# Dashboard_rev3.net
KiCad netlist of a schematic drawn in EAGLE
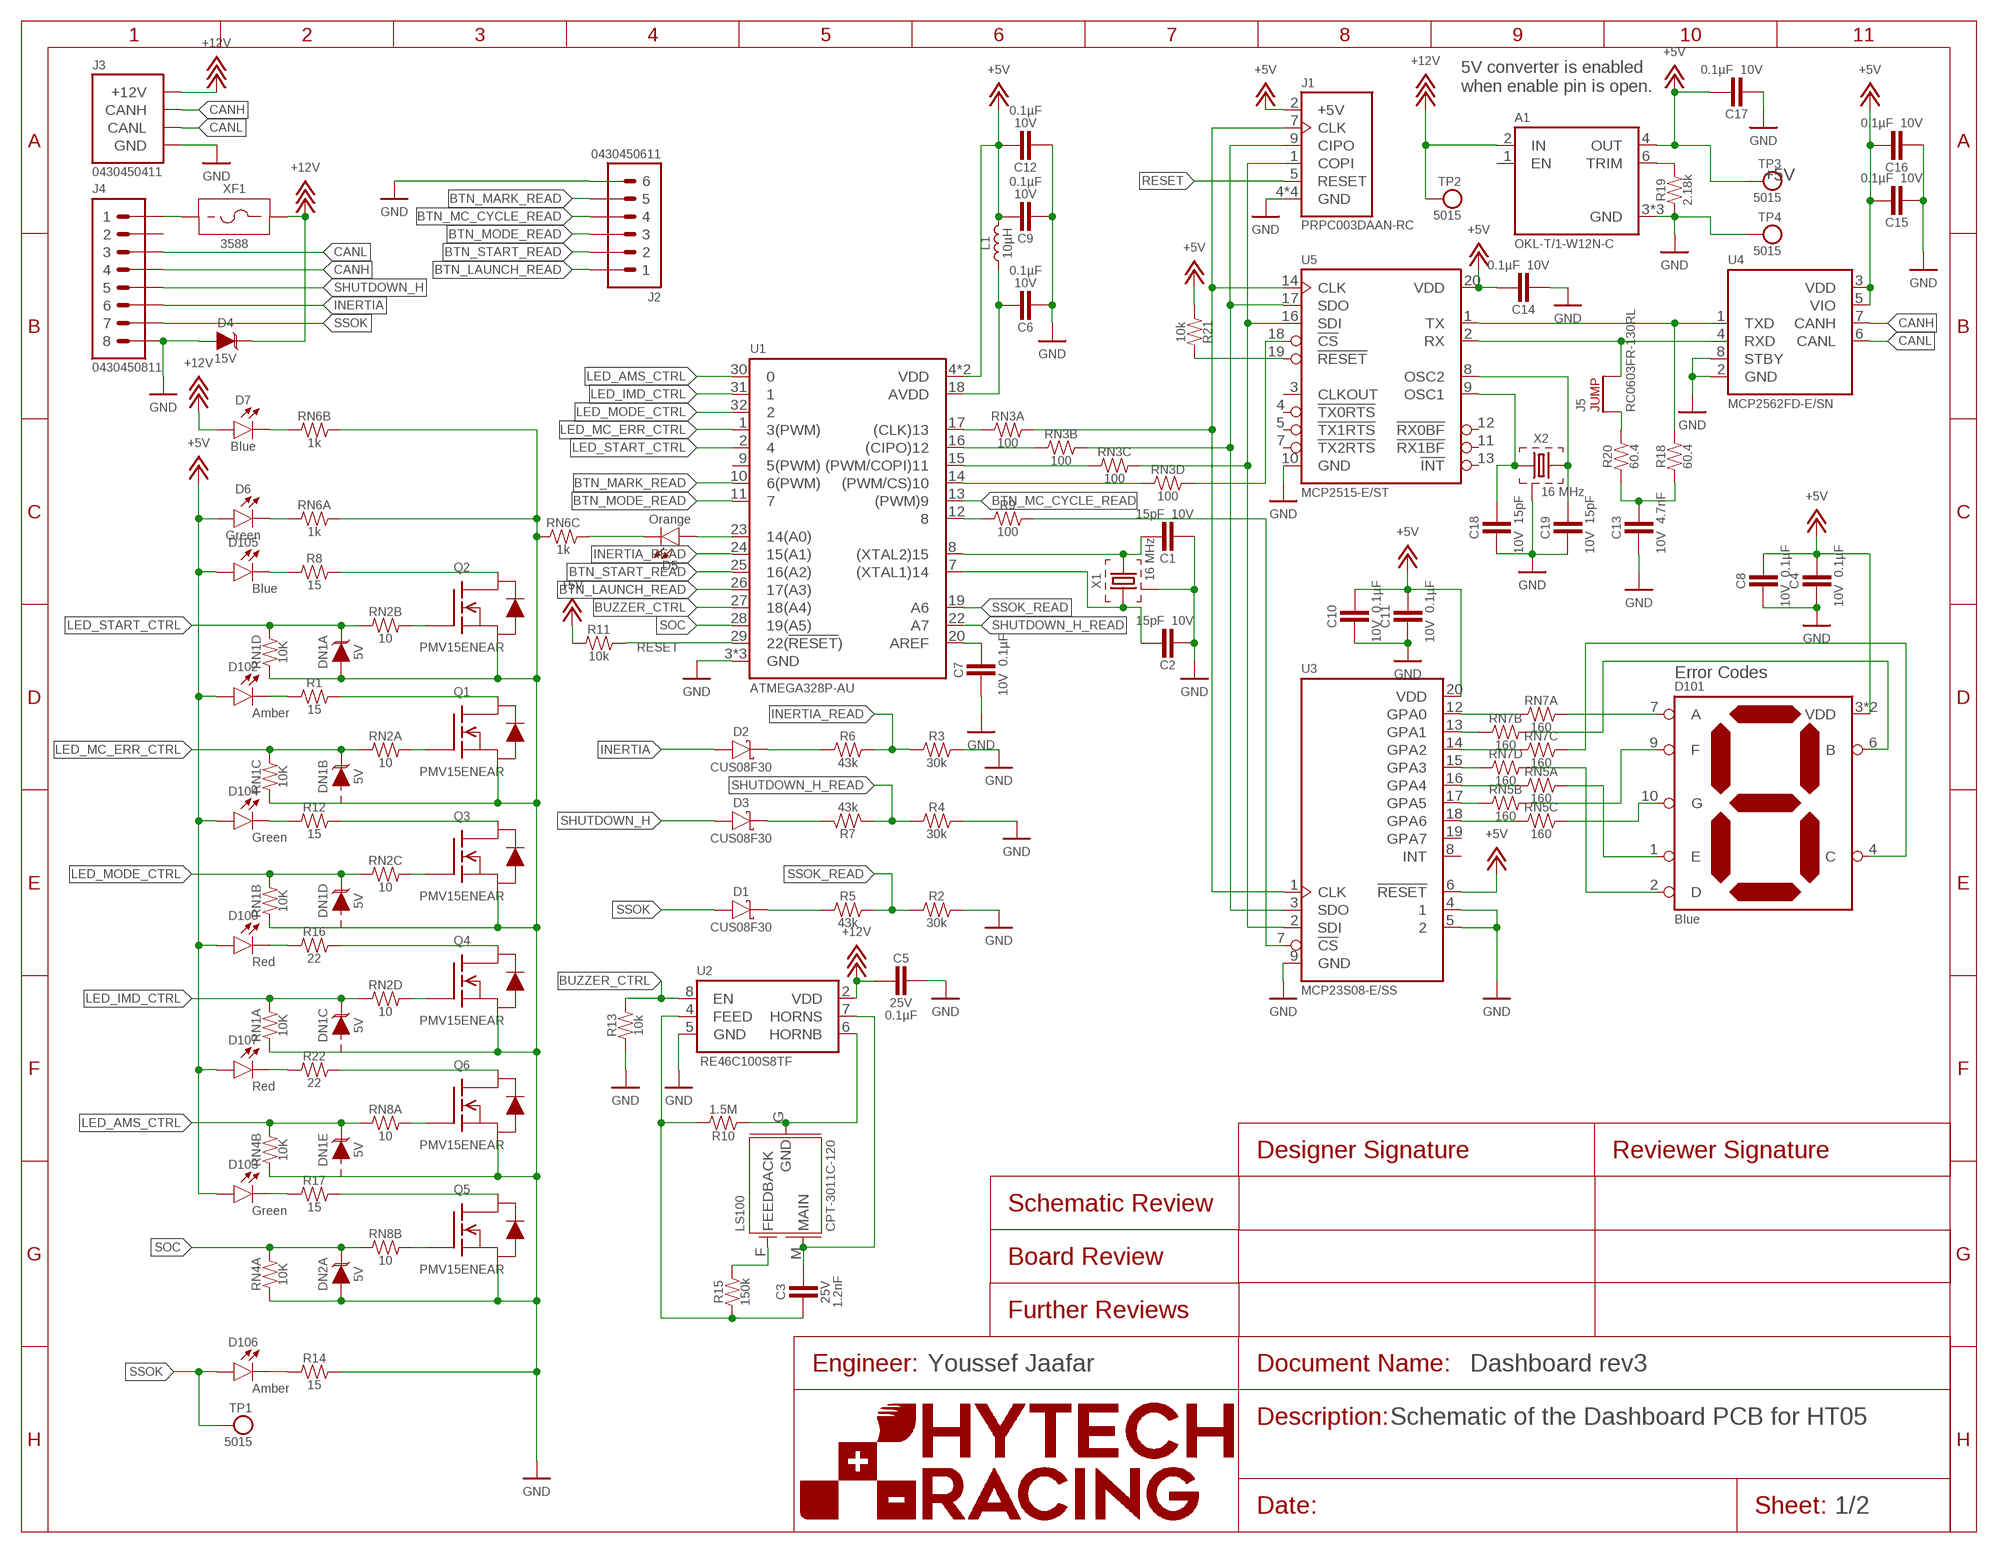
[diagram p0: schematic, sheet 1]
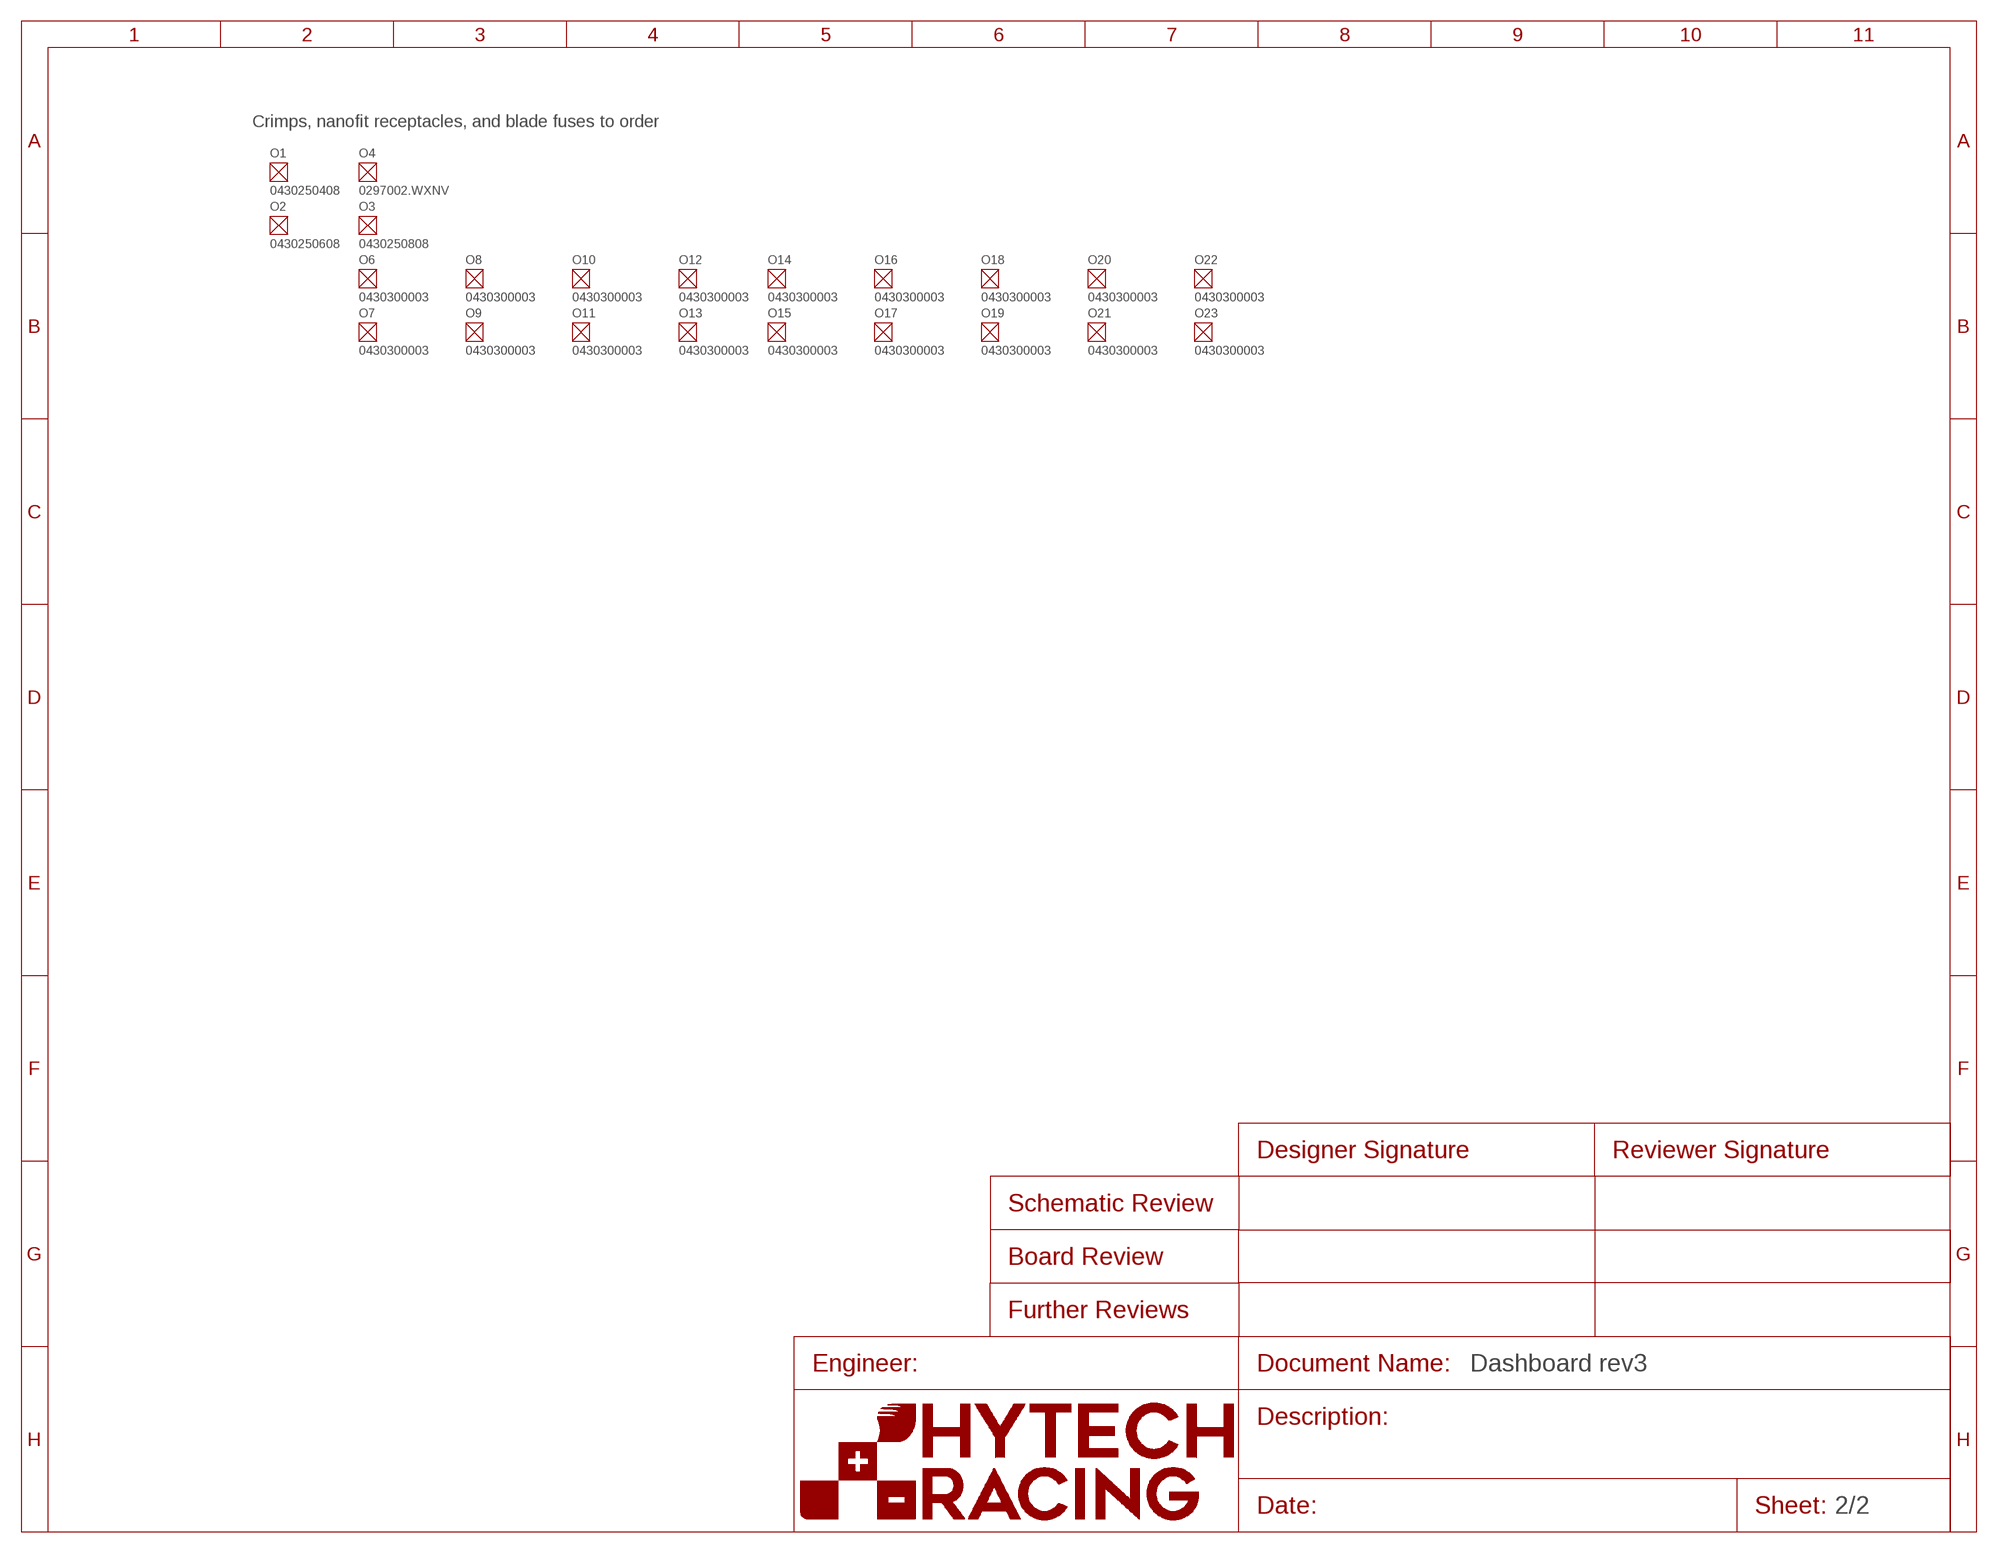
[diagram p1: schematic, sheet 2]

(export (version "E")
  (design (tool "Eeschema 10.0.6"))
  (components
    (comp (ref "A1")
      (value "OKL-T/1-W12N-COKL")
      (footprint "eagle-import:OKL-T_1-W12")
      (fields
        (field (name "MANUFACTURER") "Murata Power Solutions Inc.")
        (field (name "MPN") "OKL-T/1-W12N-C")
      )
      (libsource (lib "eagle-import") (part "OKL-OKLT/1-W12N-C"))
    )
    (comp (ref "C1")
      (value "CAPACITOR_0603_10V_15PF")
      (footprint "eagle-import:0603-CAP")
      (fields
        (field (name "CAPACITANCE") "15pF")
        (field (name "MANUFACTURER") "Vishay Vitramon")
        (field (name "MPN") "VJ0603A150FXQPW1BC")
        (field (name "TOLERANCE") "1%")
        (field (name "VOLTAGE") "10V")
      )
      (libsource (lib "eagle-import") (part "CAPACITOR_?_060310V_15PF"))
    )
    (comp (ref "C2")
      (value "CAPACITOR_0603_10V_15PF")
      (footprint "eagle-import:0603-CAP")
      (fields
        (field (name "CAPACITANCE") "15pF")
        (field (name "MANUFACTURER") "Vishay Vitramon")
        (field (name "MPN") "VJ0603A150FXQPW1BC")
        (field (name "TOLERANCE") "1%")
        (field (name "VOLTAGE") "10V")
      )
      (libsource (lib "eagle-import") (part "CAPACITOR_?_060310V_15PF"))
    )
    (comp (ref "C3")
      (value "CAPACITOR_0603_25V_1.2NF")
      (footprint "eagle-import:0603-CAP")
      (fields
        (field (name "CAPACITANCE") "1.2nF")
        (field (name "MANUFACTURER") "YAGEO")
        (field (name "MPN") "CC0603KRX7R8BB122")
        (field (name "TOLERANCE") "10%")
        (field (name "VOLTAGE") "25V")
      )
      (libsource (lib "eagle-import") (part "CAPACITOR_?_060325V_1.2NF"))
    )
    (comp (ref "C4")
      (value "CAPACITOR_0603_10V_0.1UF")
      (footprint "eagle-import:0603-CAP")
      (fields
        (field (name "CAPACITANCE") "0.1µF")
        (field (name "MANUFACTURER") "Vishay Vitramon")
        (field (name "MPN") "VJ0603Y104JXQPW1BC")
        (field (name "TOLERANCE") "5%")
        (field (name "VOLTAGE") "10V")
      )
      (libsource (lib "eagle-import") (part "CAPACITOR_?_060310V_0.1UF"))
    )
    (comp (ref "C5")
      (value "CAPACITOR_0603_25V_0.1UF")
      (footprint "eagle-import:0603-CAP")
      (fields
        (field (name "CAPACITANCE") "0.1µF")
        (field (name "MANUFACTURER") "Samsung Electro-Mechanics")
        (field (name "MPN") "CL10B104KA8NNNC")
        (field (name "TOLERANCE") "10%")
        (field (name "VOLTAGE") "25V")
      )
      (libsource (lib "eagle-import") (part "CAPACITOR_?_060325V_0.1UF"))
    )
    (comp (ref "C6")
      (value "CAPACITOR_0603_10V_0.1UF")
      (footprint "eagle-import:0603-CAP")
      (fields
        (field (name "CAPACITANCE") "0.1µF")
        (field (name "MANUFACTURER") "Vishay Vitramon")
        (field (name "MPN") "VJ0603Y104JXQPW1BC")
        (field (name "TOLERANCE") "5%")
        (field (name "VOLTAGE") "10V")
      )
      (libsource (lib "eagle-import") (part "CAPACITOR_?_060310V_0.1UF"))
    )
    (comp (ref "C7")
      (value "CAPACITOR_0603_10V_0.1UF")
      (footprint "eagle-import:0603-CAP")
      (fields
        (field (name "CAPACITANCE") "0.1µF")
        (field (name "MANUFACTURER") "Vishay Vitramon")
        (field (name "MPN") "VJ0603Y104JXQPW1BC")
        (field (name "TOLERANCE") "5%")
        (field (name "VOLTAGE") "10V")
      )
      (libsource (lib "eagle-import") (part "CAPACITOR_?_060310V_0.1UF"))
    )
    (comp (ref "C8")
      (value "CAPACITOR_0603_10V_0.1UF")
      (footprint "eagle-import:0603-CAP")
      (fields
        (field (name "CAPACITANCE") "0.1µF")
        (field (name "MANUFACTURER") "Vishay Vitramon")
        (field (name "MPN") "VJ0603Y104JXQPW1BC")
        (field (name "TOLERANCE") "5%")
        (field (name "VOLTAGE") "10V")
      )
      (libsource (lib "eagle-import") (part "CAPACITOR_?_060310V_0.1UF"))
    )
    (comp (ref "C9")
      (value "CAPACITOR_0603_10V_0.1UF")
      (footprint "eagle-import:0603-CAP")
      (fields
        (field (name "CAPACITANCE") "0.1µF")
        (field (name "MANUFACTURER") "Vishay Vitramon")
        (field (name "MPN") "VJ0603Y104JXQPW1BC")
        (field (name "TOLERANCE") "5%")
        (field (name "VOLTAGE") "10V")
      )
      (libsource (lib "eagle-import") (part "CAPACITOR_?_060310V_0.1UF"))
    )
    (comp (ref "C10")
      (value "CAPACITOR_0603_10V_0.1UF")
      (footprint "eagle-import:0603-CAP")
      (fields
        (field (name "CAPACITANCE") "0.1µF")
        (field (name "MANUFACTURER") "Vishay Vitramon")
        (field (name "MPN") "VJ0603Y104JXQPW1BC")
        (field (name "TOLERANCE") "5%")
        (field (name "VOLTAGE") "10V")
      )
      (libsource (lib "eagle-import") (part "CAPACITOR_?_060310V_0.1UF"))
    )
    (comp (ref "C11")
      (value "CAPACITOR_0603_10V_0.1UF")
      (footprint "eagle-import:0603-CAP")
      (fields
        (field (name "CAPACITANCE") "0.1µF")
        (field (name "MANUFACTURER") "Vishay Vitramon")
        (field (name "MPN") "VJ0603Y104JXQPW1BC")
        (field (name "TOLERANCE") "5%")
        (field (name "VOLTAGE") "10V")
      )
      (libsource (lib "eagle-import") (part "CAPACITOR_?_060310V_0.1UF"))
    )
    (comp (ref "C12")
      (value "CAPACITOR_0603_10V_0.1UF")
      (footprint "eagle-import:0603-CAP")
      (fields
        (field (name "CAPACITANCE") "0.1µF")
        (field (name "MANUFACTURER") "Vishay Vitramon")
        (field (name "MPN") "VJ0603Y104JXQPW1BC")
        (field (name "TOLERANCE") "5%")
        (field (name "VOLTAGE") "10V")
      )
      (libsource (lib "eagle-import") (part "CAPACITOR_?_060310V_0.1UF"))
    )
    (comp (ref "C13")
      (value "CAPACITOR_0603_10V_4.7NF")
      (footprint "eagle-import:0603-CAP")
      (fields
        (field (name "CAPACITANCE") "4.7nF")
        (field (name "MANUFACTURER") "Würth Elektronik")
        (field (name "MPN") "885012206012")
        (field (name "TOLERANCE") "10%")
        (field (name "VOLTAGE") "10V")
      )
      (libsource (lib "eagle-import") (part "CAPACITOR_?_060310V_4.7NF"))
    )
    (comp (ref "C14")
      (value "CAPACITOR_0603_10V_0.1UF")
      (footprint "eagle-import:0603-CAP")
      (fields
        (field (name "CAPACITANCE") "0.1µF")
        (field (name "MANUFACTURER") "Vishay Vitramon")
        (field (name "MPN") "VJ0603Y104JXQPW1BC")
        (field (name "TOLERANCE") "5%")
        (field (name "VOLTAGE") "10V")
      )
      (libsource (lib "eagle-import") (part "CAPACITOR_?_060310V_0.1UF"))
    )
    (comp (ref "C15")
      (value "CAPACITOR_0603_10V_0.1UF")
      (footprint "eagle-import:0603-CAP")
      (fields
        (field (name "CAPACITANCE") "0.1µF")
        (field (name "MANUFACTURER") "Vishay Vitramon")
        (field (name "MPN") "VJ0603Y104JXQPW1BC")
        (field (name "TOLERANCE") "5%")
        (field (name "VOLTAGE") "10V")
      )
      (libsource (lib "eagle-import") (part "CAPACITOR_?_060310V_0.1UF"))
    )
    (comp (ref "C16")
      (value "CAPACITOR_0603_10V_0.1UF")
      (footprint "eagle-import:0603-CAP")
      (fields
        (field (name "CAPACITANCE") "0.1µF")
        (field (name "MANUFACTURER") "Vishay Vitramon")
        (field (name "MPN") "VJ0603Y104JXQPW1BC")
        (field (name "TOLERANCE") "5%")
        (field (name "VOLTAGE") "10V")
      )
      (libsource (lib "eagle-import") (part "CAPACITOR_?_060310V_0.1UF"))
    )
    (comp (ref "C17")
      (value "CAPACITOR_0603_10V_0.1UF")
      (footprint "eagle-import:0603-CAP")
      (fields
        (field (name "CAPACITANCE") "0.1µF")
        (field (name "MANUFACTURER") "Vishay Vitramon")
        (field (name "MPN") "VJ0603Y104JXQPW1BC")
        (field (name "TOLERANCE") "5%")
        (field (name "VOLTAGE") "10V")
      )
      (libsource (lib "eagle-import") (part "CAPACITOR_?_060310V_0.1UF"))
    )
    (comp (ref "C18")
      (value "CAPACITOR_0603_10V_15PF")
      (footprint "eagle-import:0603-CAP")
      (fields
        (field (name "CAPACITANCE") "15pF")
        (field (name "MANUFACTURER") "Vishay Vitramon")
        (field (name "MPN") "VJ0603A150FXQPW1BC")
        (field (name "TOLERANCE") "1%")
        (field (name "VOLTAGE") "10V")
      )
      (libsource (lib "eagle-import") (part "CAPACITOR_?_060310V_15PF"))
    )
    (comp (ref "C19")
      (value "CAPACITOR_0603_10V_15PF")
      (footprint "eagle-import:0603-CAP")
      (fields
        (field (name "CAPACITANCE") "15pF")
        (field (name "MANUFACTURER") "Vishay Vitramon")
        (field (name "MPN") "VJ0603A150FXQPW1BC")
        (field (name "TOLERANCE") "1%")
        (field (name "VOLTAGE") "10V")
      )
      (libsource (lib "eagle-import") (part "CAPACITOR_?_060310V_15PF"))
    )
    (comp (ref "D1")
      (value "SCHOTTKY_SOD323_30V")
      (footprint "eagle-import:SOD-323")
      (fields
        (field (name "MANUFACTURER") "Toshiba Semiconductor and Storage")
        (field (name "MPN") "CUS08F30")
        (field (name "VOLTAGE") "30V")
      )
      (libsource (lib "eagle-import") (part "SCHOTTKY_?_SOD32330V"))
    )
    (comp (ref "D2")
      (value "SCHOTTKY_SOD323_30V")
      (footprint "eagle-import:SOD-323")
      (fields
        (field (name "MANUFACTURER") "Toshiba Semiconductor and Storage")
        (field (name "MPN") "CUS08F30")
        (field (name "VOLTAGE") "30V")
      )
      (libsource (lib "eagle-import") (part "SCHOTTKY_?_SOD32330V"))
    )
    (comp (ref "D3")
      (value "SCHOTTKY_SOD323_30V")
      (footprint "eagle-import:SOD-323")
      (fields
        (field (name "MANUFACTURER") "Toshiba Semiconductor and Storage")
        (field (name "MPN") "CUS08F30")
        (field (name "VOLTAGE") "30V")
      )
      (libsource (lib "eagle-import") (part "SCHOTTKY_?_SOD32330V"))
    )
    (comp (ref "D4")
      (value "TVS_15V")
      (footprint "eagle-import:SOT-23")
      (fields
        (field (name "MANUFACTURER") "Vishay General Semiconductor - Diodes Division")
        (field (name "MPN") "GSOT15-E3-08")
        (field (name "VOLTAGE") "15V")
      )
      (libsource (lib "eagle-import") (part "TVS_15V"))
    )
    (comp (ref "D5")
      (value "LED_0603_ORANGE")
      (footprint "eagle-import:0603-LED")
      (fields
        (field (name "COLOR") "Orange")
        (field (name "MANUFACTURER") "Kingbright")
        (field (name "MPN") "APT1608SECK")
      )
      (libsource (lib "eagle-import") (part "LED_?_0603ORANGE"))
    )
    (comp (ref "D6")
      (value "LED_0603_GREEN")
      (footprint "eagle-import:0603-LED")
      (fields
        (field (name "COLOR") "Green")
        (field (name "MANUFACTURER") "Kingbright")
        (field (name "MPN") "APT1608ZGCK")
      )
      (libsource (lib "eagle-import") (part "LED_?_0603GREEN"))
    )
    (comp (ref "D7")
      (value "LED_0603_BLUE")
      (footprint "eagle-import:0603-LED")
      (fields
        (field (name "COLOR") "Blue")
        (field (name "MANUFACTURER") "Kingbright")
        (field (name "MPN") "APT1608VBC/D")
      )
      (libsource (lib "eagle-import") (part "LED_?_0603BLUE"))
    )
    (comp (ref "D100")
      (value "LED_2835_RED")
      (footprint "eagle-import:2835-LED")
      (fields
        (field (name "COLOR") "Red")
        (field (name "MANUFACTURER") "Lumileds")
        (field (name "MPN") "L128-RED1003500000")
      )
      (libsource (lib "eagle-import") (part "LED_?_2835RED"))
    )
    (comp (ref "D101")
      (value "LED_7_SEGMENT_BLUE_DSM7TA")
      (footprint "eagle-import:DSM7T")
      (fields
        (field (name "COLOR") "Blue")
        (field (name "MANUFACTURER") "Visual Communications Company")
        (field (name "MPN") "DSM7TA56106T")
      )
      (libsource (lib "eagle-import") (part "LED_7_SEGMENT_DSM7TABLUE_"))
    )
    (comp (ref "D102")
      (value "LED_2835_AMBER")
      (footprint "eagle-import:2835-LED")
      (fields
        (field (name "COLOR") "Amber")
        (field (name "MANUFACTURER") "Lumileds")
        (field (name "MPN") "L128-PCA1003500000")
      )
      (libsource (lib "eagle-import") (part "LED_?_2835AMBER"))
    )
    (comp (ref "D103")
      (value "LED_2835_GREEN")
      (footprint "eagle-import:2835-LED")
      (fields
        (field (name "COLOR") "Green")
        (field (name "MANUFACTURER") "Lumileds")
        (field (name "MPN") "L128-GRN1003500000")
      )
      (libsource (lib "eagle-import") (part "LED_?_2835GREEN"))
    )
    (comp (ref "D104")
      (value "LED_2835_GREEN")
      (footprint "eagle-import:2835-LED")
      (fields
        (field (name "COLOR") "Green")
        (field (name "MANUFACTURER") "Lumileds")
        (field (name "MPN") "L128-GRN1003500000")
      )
      (libsource (lib "eagle-import") (part "LED_?_2835GREEN"))
    )
    (comp (ref "D105")
      (value "LED_2835_BLUE")
      (footprint "eagle-import:2835-LED")
      (fields
        (field (name "COLOR") "Blue")
        (field (name "MANUFACTURER") "Lumileds")
        (field (name "MPN") "L128-BLU1003500000")
      )
      (libsource (lib "eagle-import") (part "LED_?_2835BLUE"))
    )
    (comp (ref "D106")
      (value "LED_2835_AMBER")
      (footprint "eagle-import:2835-LED")
      (fields
        (field (name "COLOR") "Amber")
        (field (name "MANUFACTURER") "Lumileds")
        (field (name "MPN") "L128-PCA1003500000")
      )
      (libsource (lib "eagle-import") (part "LED_?_2835AMBER"))
    )
    (comp (ref "D107")
      (value "LED_2835_RED")
      (footprint "eagle-import:2835-LED")
      (fields
        (field (name "COLOR") "Red")
        (field (name "MANUFACTURER") "Lumileds")
        (field (name "MPN") "L128-RED1003500000")
      )
      (libsource (lib "eagle-import") (part "LED_?_2835RED"))
    )
    (comp (ref "DN1")
      (value "TVS_ARRAY_5V")
      (footprint "eagle-import:SOT-363")
      (fields
        (field (name "MANUFACTURER") "Vishay General Semiconductor - Diodes Division")
        (field (name "MPN") "VESD05A5-06G-G3-08")
        (field (name "VOLTAGE") "5V")
      )
      (libsource (lib "eagle-import") (part "TVS_ARRAY_5V"))
    )
    (comp (ref "DN2")
      (value "TVS_ARRAY_5V")
      (footprint "eagle-import:SOT-363")
      (fields
        (field (name "MANUFACTURER") "Vishay General Semiconductor - Diodes Division")
        (field (name "MPN") "VESD05A5-06G-G3-08")
        (field (name "VOLTAGE") "5V")
      )
      (libsource (lib "eagle-import") (part "TVS_ARRAY_5V"))
    )
    (comp (ref "J1")
      (value "CONNECTOR-AVR-ISP_2X05_SMD")
      (footprint "eagle-import:2X05_SMD")
      (fields
        (field (name "MPN") "PRPC003DAAN-RC")
        (field (name "MANUFACTURER") "Sullins Connector Solutions")
      )
      (libsource (lib "eagle-import") (part "CONNECTOR-AVR-ISP_?2X05_SMD"))
    )
    (comp (ref "J2")
      (value "CONNECTOR-6_μF_S_RA_")
      (footprint "eagle-import:MOLEX_MICROFIT_SMD_RIGHTANGLE_06_DUAL")
      (fields (field (name "MPN") "0430450611") (field (name "MANUFACTURER") "Molex"))
      (libsource (lib "eagle-import") (part "CONNECTOR-6_?_μF_S_RA"))
    )
    (comp (ref "J3")
      (value "CONNECTOR-CAN_μF_S_RA_")
      (footprint "eagle-import:MOLEX_MICROFIT_SMD_RIGHTANGLE_04_DUAL")
      (fields (field (name "MPN") "0430450411") (field (name "MANUFACTURER") "Molex"))
      (libsource (lib "eagle-import") (part "CONNECTOR-CAN_?_μF_S_RA"))
    )
    (comp (ref "J4")
      (value "CONNECTOR-8_μF_S_RA_")
      (footprint "eagle-import:MOLEX_MICROFIT_SMD_RIGHTANGLE_08_DUAL")
      (fields (field (name "MPN") "0430450811") (field (name "MANUFACTURER") "Molex"))
      (libsource (lib "eagle-import") (part "CONNECTOR-8_?_μF_S_RA"))
    )
    (comp (ref "J5")
      (value "JUMPER_0603_")
      (footprint "eagle-import:0603-RES")
      (fields (field (name "MPN") "RC0603FR-130RL") (field (name "MANUFACTURER") "YAGEO"))
      (libsource (lib "eagle-import") (part "JUMPER_?_0603"))
    )
    (comp (ref "L1")
      (value "INDUCTOR_LQM18DH100M70_10UH")
      (footprint "eagle-import:0603-IND")
      (fields
        (field (name "INDUCTANCE") "10µH")
        (field (name "MANUFACTURER") "Murata Electronics")
        (field (name "MPN") "LQM18DH100M70L")
        (field (name "TOLERANCE") "20%")
      )
      (libsource (lib "eagle-import") (part "INDUCTOR_?_LQM18DH100M7010UH"))
    )
    (comp (ref "LS100")
      (value "BUZZER_3_PIN_CPT-3011C-120")
      (footprint "eagle-import:CPT-3011C-120")
      (fields
        (field (name "MANUFACTURER") "CUI Devices")
        (field (name "MPN") "CPT-3011C-120")
        (field (name "VOLTAGE") "12V")
      )
      (libsource (lib "eagle-import") (part "BUZZER_3_PIN_CPT-3011C-120"))
    )
    (comp (ref "Q1")
      (value "TRANSISTOR_N_MOS__PMV15ENEA")
      (footprint "eagle-import:SOT-23")
      (fields (field (name "MANUFACTURER") "Nexperia USA Inc.") (field (name "MPN") "PMV15ENEAR"))
      (libsource (lib "eagle-import") (part "TRANSISTOR_N_MOS_?_PMV15ENEA"))
    )
    (comp (ref "Q2")
      (value "TRANSISTOR_N_MOS__PMV15ENEA")
      (footprint "eagle-import:SOT-23")
      (fields (field (name "MANUFACTURER") "Nexperia USA Inc.") (field (name "MPN") "PMV15ENEAR"))
      (libsource (lib "eagle-import") (part "TRANSISTOR_N_MOS_?_PMV15ENEA"))
    )
    (comp (ref "Q3")
      (value "TRANSISTOR_N_MOS__PMV15ENEA")
      (footprint "eagle-import:SOT-23")
      (fields (field (name "MANUFACTURER") "Nexperia USA Inc.") (field (name "MPN") "PMV15ENEAR"))
      (libsource (lib "eagle-import") (part "TRANSISTOR_N_MOS_?_PMV15ENEA"))
    )
    (comp (ref "Q4")
      (value "TRANSISTOR_N_MOS__PMV15ENEA")
      (footprint "eagle-import:SOT-23")
      (fields (field (name "MANUFACTURER") "Nexperia USA Inc.") (field (name "MPN") "PMV15ENEAR"))
      (libsource (lib "eagle-import") (part "TRANSISTOR_N_MOS_?_PMV15ENEA"))
    )
    (comp (ref "Q5")
      (value "TRANSISTOR_N_MOS__PMV15ENEA")
      (footprint "eagle-import:SOT-23")
      (fields (field (name "MANUFACTURER") "Nexperia USA Inc.") (field (name "MPN") "PMV15ENEAR"))
      (libsource (lib "eagle-import") (part "TRANSISTOR_N_MOS_?_PMV15ENEA"))
    )
    (comp (ref "Q6")
      (value "TRANSISTOR_N_MOS__PMV15ENEA")
      (footprint "eagle-import:SOT-23")
      (fields (field (name "MANUFACTURER") "Nexperia USA Inc.") (field (name "MPN") "PMV15ENEAR"))
      (libsource (lib "eagle-import") (part "TRANSISTOR_N_MOS_?_PMV15ENEA"))
    )
    (comp (ref "R1")
      (value "RESISTOR_0603_15")
      (footprint "eagle-import:0603-RES")
      (fields
        (field (name "MANUFACTURER") "Vishay Dale")
        (field (name "MPN") "CRCW060315R0FKEAHP")
        (field (name "POWER") "0.33W")
        (field (name "RESISTANCE") "15")
      )
      (libsource (lib "eagle-import") (part "RESISTOR_?_060315"))
    )
    (comp (ref "R2")
      (value "RESISTOR_0603_30K")
      (footprint "eagle-import:0603-RES")
      (fields
        (field (name "MANUFACTURER") "Panasonic Electronic Components")
        (field (name "MPN") "ERA-3ARB303V")
        (field (name "POWER") "0.1W")
        (field (name "RESISTANCE") "30k")
      )
      (libsource (lib "eagle-import") (part "RESISTOR_?_060330K"))
    )
    (comp (ref "R3")
      (value "RESISTOR_0603_30K")
      (footprint "eagle-import:0603-RES")
      (fields
        (field (name "MANUFACTURER") "Panasonic Electronic Components")
        (field (name "MPN") "ERA-3ARB303V")
        (field (name "POWER") "0.1W")
        (field (name "RESISTANCE") "30k")
      )
      (libsource (lib "eagle-import") (part "RESISTOR_?_060330K"))
    )
    (comp (ref "R4")
      (value "RESISTOR_0603_30K")
      (footprint "eagle-import:0603-RES")
      (fields
        (field (name "MANUFACTURER") "Panasonic Electronic Components")
        (field (name "MPN") "ERA-3ARB303V")
        (field (name "POWER") "0.1W")
        (field (name "RESISTANCE") "30k")
      )
      (libsource (lib "eagle-import") (part "RESISTOR_?_060330K"))
    )
    (comp (ref "R5")
      (value "RESISTOR_0603_43K")
      (footprint "eagle-import:0603-RES")
      (fields
        (field (name "MANUFACTURER") "Yageo")
        (field (name "MPN") "RC0603FR-0743KL")
        (field (name "POWER") "0.1W")
        (field (name "RESISTANCE") "43k")
      )
      (libsource (lib "eagle-import") (part "RESISTOR_?_060343K"))
    )
    (comp (ref "R6")
      (value "RESISTOR_0603_43K")
      (footprint "eagle-import:0603-RES")
      (fields
        (field (name "MANUFACTURER") "Yageo")
        (field (name "MPN") "RC0603FR-0743KL")
        (field (name "POWER") "0.1W")
        (field (name "RESISTANCE") "43k")
      )
      (libsource (lib "eagle-import") (part "RESISTOR_?_060343K"))
    )
    (comp (ref "R7")
      (value "RESISTOR_0603_43K")
      (footprint "eagle-import:0603-RES")
      (fields
        (field (name "MANUFACTURER") "Yageo")
        (field (name "MPN") "RC0603FR-0743KL")
        (field (name "POWER") "0.1W")
        (field (name "RESISTANCE") "43k")
      )
      (libsource (lib "eagle-import") (part "RESISTOR_?_060343K"))
    )
    (comp (ref "R8")
      (value "RESISTOR_0603_15")
      (footprint "eagle-import:0603-RES")
      (fields
        (field (name "MANUFACTURER") "Vishay Dale")
        (field (name "MPN") "CRCW060315R0FKEAHP")
        (field (name "POWER") "0.33W")
        (field (name "RESISTANCE") "15")
      )
      (libsource (lib "eagle-import") (part "RESISTOR_?_060315"))
    )
    (comp (ref "R9")
      (value "RESISTOR_0603_100")
      (footprint "eagle-import:0603-RES")
      (fields
        (field (name "MANUFACTURER") "Yageo")
        (field (name "MPN") "RC0603FR-07100RL")
        (field (name "POWER") "0.1W")
        (field (name "RESISTANCE") "100")
      )
      (libsource (lib "eagle-import") (part "RESISTOR_?_0603100"))
    )
    (comp (ref "R10")
      (value "RESISTOR_0603_1.5M")
      (footprint "eagle-import:0603-RES")
      (fields
        (field (name "MANUFACTURER") "Yageo")
        (field (name "MPN") "RC0603FR-071M5L")
        (field (name "POWER") "0.1W")
        (field (name "RESISTANCE") "1.5M")
      )
      (libsource (lib "eagle-import") (part "RESISTOR_?_06031.5M"))
    )
    (comp (ref "R11")
      (value "RESISTOR_0603_10K")
      (footprint "eagle-import:0603-RES")
      (fields
        (field (name "MANUFACTURER") "Yageo")
        (field (name "MPN") "RC0603FR-0710KL")
        (field (name "POWER") "0.1W")
        (field (name "RESISTANCE") "10k")
      )
      (libsource (lib "eagle-import") (part "RESISTOR_?_060310K"))
    )
    (comp (ref "R12")
      (value "RESISTOR_0603_15")
      (footprint "eagle-import:0603-RES")
      (fields
        (field (name "MANUFACTURER") "Vishay Dale")
        (field (name "MPN") "CRCW060315R0FKEAHP")
        (field (name "POWER") "0.33W")
        (field (name "RESISTANCE") "15")
      )
      (libsource (lib "eagle-import") (part "RESISTOR_?_060315"))
    )
    (comp (ref "R13")
      (value "RESISTOR_0603_10K")
      (footprint "eagle-import:0603-RES")
      (fields
        (field (name "MANUFACTURER") "Yageo")
        (field (name "MPN") "RC0603FR-0710KL")
        (field (name "POWER") "0.1W")
        (field (name "RESISTANCE") "10k")
      )
      (libsource (lib "eagle-import") (part "RESISTOR_?_060310K"))
    )
    (comp (ref "R14")
      (value "RESISTOR_0603_15")
      (footprint "eagle-import:0603-RES")
      (fields
        (field (name "MANUFACTURER") "Vishay Dale")
        (field (name "MPN") "CRCW060315R0FKEAHP")
        (field (name "POWER") "0.33W")
        (field (name "RESISTANCE") "15")
      )
      (libsource (lib "eagle-import") (part "RESISTOR_?_060315"))
    )
    (comp (ref "R15")
      (value "RESISTOR_0603_150K")
      (footprint "eagle-import:0603-RES")
      (fields
        (field (name "MANUFACTURER") "Panasonic Electronic Components")
        (field (name "MPN") "ERA-3AEB154V")
        (field (name "POWER") "0.1W")
        (field (name "RESISTANCE") "150k")
      )
      (libsource (lib "eagle-import") (part "RESISTOR_?_0603150K"))
    )
    (comp (ref "R16")
      (value "RESISTOR_0805_22")
      (footprint "eagle-import:0805-RES")
      (fields
        (field (name "MANUFACTURER") "Panasonic Electronic Components")
        (field (name "MPN") "ERJ-P06F22R0V")
        (field (name "POWER") "0.5W")
        (field (name "RESISTANCE") "22")
      )
      (libsource (lib "eagle-import") (part "RESISTOR_?_080522"))
    )
    (comp (ref "R17")
      (value "RESISTOR_0603_15")
      (footprint "eagle-import:0603-RES")
      (fields
        (field (name "MANUFACTURER") "Vishay Dale")
        (field (name "MPN") "CRCW060315R0FKEAHP")
        (field (name "POWER") "0.33W")
        (field (name "RESISTANCE") "15")
      )
      (libsource (lib "eagle-import") (part "RESISTOR_?_060315"))
    )
    (comp (ref "R18")
      (value "RESISTOR_0603_60.4")
      (footprint "eagle-import:0603-RES")
      (fields
        (field (name "MANUFACTURER") "Yageo")
        (field (name "MPN") "RC0603FR-0760R4L")
        (field (name "POWER") "0.1W")
        (field (name "RESISTANCE") "60.4")
      )
      (libsource (lib "eagle-import") (part "RESISTOR_?_060360.4"))
    )
    (comp (ref "R19")
      (value "RESISTOR_0603_2.18K")
      (footprint "eagle-import:0603-RES")
      (fields
        (field (name "MANUFACTURER") "YAGEO")
        (field (name "MPN") "RT0805BRD072K18L")
        (field (name "POWER") "0.125W")
        (field (name "RESISTANCE") "2.18k")
      )
      (libsource (lib "eagle-import") (part "RESISTOR_?_06032.18K"))
    )
    (comp (ref "R20")
      (value "RESISTOR_0603_60.4")
      (footprint "eagle-import:0603-RES")
      (fields
        (field (name "MANUFACTURER") "Yageo")
        (field (name "MPN") "RC0603FR-0760R4L")
        (field (name "POWER") "0.1W")
        (field (name "RESISTANCE") "60.4")
      )
      (libsource (lib "eagle-import") (part "RESISTOR_?_060360.4"))
    )
    (comp (ref "R21")
      (value "RESISTOR_0603_10K")
      (footprint "eagle-import:0603-RES")
      (fields
        (field (name "MANUFACTURER") "Yageo")
        (field (name "MPN") "RC0603FR-0710KL")
        (field (name "POWER") "0.1W")
        (field (name "RESISTANCE") "10k")
      )
      (libsource (lib "eagle-import") (part "RESISTOR_?_060310K"))
    )
    (comp (ref "R22")
      (value "RESISTOR_0805_22")
      (footprint "eagle-import:0805-RES")
      (fields
        (field (name "MANUFACTURER") "Panasonic Electronic Components")
        (field (name "MPN") "ERJ-P06F22R0V")
        (field (name "POWER") "0.5W")
        (field (name "RESISTANCE") "22")
      )
      (libsource (lib "eagle-import") (part "RESISTOR_?_080522"))
    )
    (comp (ref "RN1")
      (value "RESISTOR_NETWORK_4_10K")
      (footprint "eagle-import:1206-RES-ARRAY")
      (fields
        (field (name "MANUFACTURER") "Yageo")
        (field (name "MPN") "TC164-FR-0710KL")
        (field (name "POWER") "1/16W")
        (field (name "RESISTANCE") "10K")
      )
      (libsource (lib "eagle-import") (part "RESISTOR_NETWORK_4_10K"))
    )
    (comp (ref "RN2")
      (value "RESISTOR_NETWORK_4_10")
      (footprint "eagle-import:1206-RES-ARRAY")
      (fields
        (field (name "MANUFACTURER") "Bourns Inc.")
        (field (name "MPN") "CAT16-100J4LF")
        (field (name "POWER") "1/16W")
        (field (name "RESISTANCE") "10")
      )
      (libsource (lib "eagle-import") (part "RESISTOR_NETWORK_4_10"))
    )
    (comp (ref "RN3")
      (value "RESISTOR_NETWORK_4_100")
      (footprint "eagle-import:1206-RES-ARRAY")
      (fields
        (field (name "MANUFACTURER") "Bourns Inc.")
        (field (name "MPN") "CAT16-1000F4LF")
        (field (name "POWER") "1/16W")
        (field (name "RESISTANCE") "100")
      )
      (libsource (lib "eagle-import") (part "RESISTOR_NETWORK_4_100"))
    )
    (comp (ref "RN4")
      (value "RESISTOR_NETWORK_4_10K")
      (footprint "eagle-import:1206-RES-ARRAY")
      (fields
        (field (name "MANUFACTURER") "Yageo")
        (field (name "MPN") "TC164-FR-0710KL")
        (field (name "POWER") "1/16W")
        (field (name "RESISTANCE") "10K")
      )
      (libsource (lib "eagle-import") (part "RESISTOR_NETWORK_4_10K"))
    )
    (comp (ref "RN5")
      (value "RESISTOR_NETWORK_4_160")
      (footprint "eagle-import:1206-RES-ARRAY")
      (fields
        (field (name "MANUFACTURER") "Yageo")
        (field (name "MPN") "YC164-JR-07160RL")
        (field (name "POWER") "1/16W")
        (field (name "RESISTANCE") "160")
      )
      (libsource (lib "eagle-import") (part "RESISTOR_NETWORK_4_160"))
    )
    (comp (ref "RN6")
      (value "RESISTOR_NETWORK_4_1K")
      (footprint "eagle-import:1206-RES-ARRAY")
      (fields
        (field (name "MANUFACTURER") "Yageo")
        (field (name "MPN") "YC164-FR-071KL")
        (field (name "POWER") "1/16W")
        (field (name "RESISTANCE") "1k")
      )
      (libsource (lib "eagle-import") (part "RESISTOR_NETWORK_4_1K"))
    )
    (comp (ref "RN7")
      (value "RESISTOR_NETWORK_4_160")
      (footprint "eagle-import:1206-RES-ARRAY")
      (fields
        (field (name "MANUFACTURER") "Yageo")
        (field (name "MPN") "YC164-JR-07160RL")
        (field (name "POWER") "1/16W")
        (field (name "RESISTANCE") "160")
      )
      (libsource (lib "eagle-import") (part "RESISTOR_NETWORK_4_160"))
    )
    (comp (ref "RN8")
      (value "RESISTOR_NETWORK_4_10")
      (footprint "eagle-import:1206-RES-ARRAY")
      (fields
        (field (name "MANUFACTURER") "Bourns Inc.")
        (field (name "MPN") "CAT16-100J4LF")
        (field (name "POWER") "1/16W")
        (field (name "RESISTANCE") "10")
      )
      (libsource (lib "eagle-import") (part "RESISTOR_NETWORK_4_10"))
    )
    (comp (ref "TP1")
      (value "TEST_POINT")
      (footprint "eagle-import:5015")
      (fields (field (name "MPN") "5015") (field (name "MANUFACTURER") "Keystone Electronics"))
      (libsource (lib "eagle-import") (part "TEST_POINT"))
    )
    (comp (ref "TP2")
      (value "TEST_POINT")
      (footprint "eagle-import:5015")
      (fields (field (name "MPN") "5015") (field (name "MANUFACTURER") "Keystone Electronics"))
      (libsource (lib "eagle-import") (part "TEST_POINT"))
    )
    (comp (ref "TP3")
      (value "TEST_POINT")
      (footprint "eagle-import:5015")
      (fields
        (field (name "MPN") "5015")
        (field (name "MANUFACTURER") "Keystone Electronics")
        (field (name "SIGNAL") "+5V")
      )
      (libsource (lib "eagle-import") (part "TEST_POINT"))
    )
    (comp (ref "TP4")
      (value "TEST_POINT")
      (footprint "eagle-import:5015")
      (fields (field (name "MPN") "5015") (field (name "MANUFACTURER") "Keystone Electronics"))
      (libsource (lib "eagle-import") (part "TEST_POINT"))
    )
    (comp (ref "U1")
      (value "ATMEGA328P-AU")
      (footprint "eagle-import:TQFP-32")
      (fields (field (name "MPN") "ATMEGA328P-AU") (field (name "MANUFACTURER") "Microchip Technology"))
      (libsource (lib "eagle-import") (part "ATMEGA328P-AU"))
    )
    (comp (ref "U2")
      (value "RE46C100")
      (footprint "eagle-import:SOIC-08(NARROW,0.15_)")
      (fields (field (name "MPN") " RE46C100S8TF") (field (name "MANUFACTURER") "Microchip Technology"))
      (libsource (lib "eagle-import") (part "RE46C100"))
    )
    (comp (ref "U3")
      (value "MCP23S08")
      (footprint "eagle-import:SSOP-20")
      (fields (field (name "MPN") "MCP23S08-E/SS") (field (name "MANUFACTURER") "Microchip Technology"))
      (libsource (lib "eagle-import") (part "MCP23S08"))
    )
    (comp (ref "U4")
      (value "MCP2562FD")
      (footprint "eagle-import:SOIC-08(NARROW,0.15_)")
      (fields (field (name "MPN") "MCP2562FD-E/SN") (field (name "MANUFACTURER") "Microchip Technology"))
      (libsource (lib "eagle-import") (part "MCP2562FD"))
    )
    (comp (ref "U5")
      (value "MCP2515")
      (footprint "eagle-import:TSSOP-20")
      (fields (field (name "MPN") "MCP2515-E/ST") (field (name "MANUFACTURER") "Microchip Technology"))
      (libsource (lib "eagle-import") (part "MCP2515"))
    )
    (comp (ref "X1")
      (value "CRYSTAL_16MHZ")
      (footprint "eagle-import:ECX-42")
      (fields
        (field (name "FREQUENCY") "16 MHz")
        (field (name "MANUFACTURER") "TXC CORPORATION")
        (field (name "MPN") "ECS-160-10-42-CKM-TR")
      )
      (libsource (lib "eagle-import") (part "CRYSTAL_16MHZ"))
    )
    (comp (ref "X2")
      (value "CRYSTAL_16MHZ")
      (footprint "eagle-import:ECX-42")
      (fields
        (field (name "FREQUENCY") "16 MHz")
        (field (name "MANUFACTURER") "TXC CORPORATION")
        (field (name "MPN") "ECS-160-10-42-CKM-TR")
      )
      (libsource (lib "eagle-import") (part "CRYSTAL_16MHZ"))
    )
    (comp (ref "XF1")
      (value "FUSE_HOLDER_MINIBLADESMD")
      (footprint "eagle-import:3588")
      (fields (field (name "MANUFACTURER") "Keystone Electronics") (field (name "MPN") "3588"))
      (libsource (lib "eagle-import") (part "FUSE_HOLDER_SMDMINIBLADE"))
    )
  )
  (nets
    (net (code "1") (name "+5V") (class "Default")
      (node (ref "A1") (pin "4") (pinfunction "OUT_4") (pintype "power_in"))
      (node (ref "C10") (pin "1") (pinfunction "1_1") (pintype "passive"))
      (node (ref "C11") (pin "1") (pinfunction "1_1") (pintype "passive"))
      (node (ref "C12") (pin "1") (pinfunction "1_1") (pintype "passive"))
      (node (ref "C14") (pin "1") (pinfunction "1_1") (pintype "passive"))
      (node (ref "C15") (pin "1") (pinfunction "1_1") (pintype "passive"))
      (node (ref "C16") (pin "1") (pinfunction "1_1") (pintype "passive"))
      (node (ref "C17") (pin "1") (pinfunction "1_1") (pintype "passive"))
      (node (ref "C4") (pin "1") (pinfunction "1_1") (pintype "passive"))
      (node (ref "C8") (pin "1") (pinfunction "1_1") (pintype "passive"))
      (node (ref "C9") (pin "1") (pinfunction "1_1") (pintype "passive"))
      (node (ref "D100") (pin "A") (pinfunction "A_A") (pintype "passive"))
      (node (ref "D101") (pin "3") (pinfunction "VDD_3") (pintype "power_in"))
      (node (ref "D101") (pin "8") (pinfunction "VDD_8") (pintype "power_in"))
      (node (ref "D102") (pin "A") (pinfunction "A_A") (pintype "passive"))
      (node (ref "D103") (pin "A") (pinfunction "A_A") (pintype "passive"))
      (node (ref "D104") (pin "A") (pinfunction "A_A") (pintype "passive"))
      (node (ref "D105") (pin "A") (pinfunction "A_A") (pintype "passive"))
      (node (ref "D107") (pin "A") (pinfunction "A_A") (pintype "passive"))
      (node (ref "D6") (pin "2") (pinfunction "A_2") (pintype "passive"))
      (node (ref "J1") (pin "2") (pinfunction "+5V_2") (pintype "power_in"))
      (node (ref "L1") (pin "2") (pinfunction "2_2") (pintype "passive"))
      (node (ref "R11") (pin "1") (pinfunction "1_1") (pintype "passive"))
      (node (ref "R21") (pin "1") (pinfunction "1_1") (pintype "passive"))
      (node (ref "TP3") (pin "1") (pinfunction "P$1_1") (pintype "passive"))
      (node (ref "U1") (pin "4") (pinfunction "VDD_4") (pintype "power_in"))
      (node (ref "U1") (pin "6") (pinfunction "VDD_6") (pintype "power_in"))
      (node (ref "U3") (pin "20") (pinfunction "VDD_20") (pintype "power_in"))
      (node (ref "U3") (pin "6") (pinfunction "~{RESET}_6") (pintype "input"))
      (node (ref "U4") (pin "3") (pinfunction "VDD_3") (pintype "power_in"))
      (node (ref "U4") (pin "5") (pinfunction "VIO_5") (pintype "power_in"))
      (node (ref "U5") (pin "20") (pinfunction "VDD_20") (pintype "power_in"))
    )
    (net (code "2") (name "+12V") (class "Default")
      (node (ref "A1") (pin "2") (pinfunction "IN_2") (pintype "input"))
      (node (ref "C5") (pin "2") (pinfunction "2_2") (pintype "passive"))
      (node (ref "D4") (pin "3") (pinfunction "C_3") (pintype "passive"))
      (node (ref "D7") (pin "2") (pinfunction "A_2") (pintype "passive"))
      (node (ref "J3") (pin "1") (pinfunction "+12V_1") (pintype "power_in"))
      (node (ref "TP2") (pin "1") (pinfunction "P$1_1") (pintype "passive"))
      (node (ref "U2") (pin "2") (pinfunction "VDD_2") (pintype "power_in"))
      (node (ref "XF1") (pin "3") (pinfunction "2_3") (pintype "passive"))
      (node (ref "XF1") (pin "4") (pinfunction "2_4") (pintype "passive"))
    )
    (net (code "3") (name "BTN_LAUNCH_READ") (class "Default")
      (node (ref "J2") (pin "1") (pinfunction "1_1") (pintype "passive"))
      (node (ref "U1") (pin "26") (pinfunction "17(A3)_26") (pintype "bidirectional"))
    )
    (net (code "4") (name "BTN_MARK_READ") (class "Default")
      (node (ref "J2") (pin "5") (pinfunction "5_5") (pintype "passive"))
      (node (ref "U1") (pin "10") (pinfunction "6(PWM)_10") (pintype "bidirectional"))
    )
    (net (code "5") (name "BTN_MC_CYCLE_READ") (class "Default")
      (node (ref "J2") (pin "4") (pinfunction "4_4") (pintype "passive"))
      (node (ref "U1") (pin "13") (pinfunction "(PWM)9_13") (pintype "bidirectional"))
    )
    (net (code "6") (name "BTN_MODE_READ") (class "Default")
      (node (ref "J2") (pin "3") (pinfunction "3_3") (pintype "passive"))
      (node (ref "U1") (pin "11") (pinfunction "7_11") (pintype "bidirectional"))
    )
    (net (code "7") (name "BTN_START_READ") (class "Default")
      (node (ref "J2") (pin "2") (pinfunction "2_2") (pintype "passive"))
      (node (ref "U1") (pin "25") (pinfunction "16(A2)_25") (pintype "bidirectional"))
    )
    (net (code "8") (name "BUZZER_CTRL") (class "Default")
      (node (ref "R13") (pin "2") (pinfunction "2_2") (pintype "passive"))
      (node (ref "U1") (pin "27") (pinfunction "18(A4)_27") (pintype "bidirectional"))
      (node (ref "U2") (pin "8") (pinfunction "EN_8") (pintype "input"))
    )
    (net (code "9") (name "CANH") (class "Default")
      (node (ref "J3") (pin "4") (pinfunction "CANH_4") (pintype "bidirectional"))
      (node (ref "J4") (pin "4") (pinfunction "4_4") (pintype "passive"))
      (node (ref "U4") (pin "7") (pinfunction "CANH_7") (pintype "bidirectional"))
    )
    (net (code "10") (name "CANL") (class "Default")
      (node (ref "J3") (pin "3") (pinfunction "CANL_3") (pintype "bidirectional"))
      (node (ref "J4") (pin "3") (pinfunction "3_3") (pintype "passive"))
      (node (ref "U4") (pin "6") (pinfunction "CANL_6") (pintype "bidirectional"))
    )
    (net (code "11") (name "GND") (class "Default")
      (node (ref "A1") (pin "11") (pinfunction "GND_11") (pintype "power_in"))
      (node (ref "A1") (pin "3") (pinfunction "GND_3") (pintype "power_in"))
      (node (ref "A1") (pin "7") (pinfunction "GND_7") (pintype "power_in"))
      (node (ref "C1") (pin "2") (pinfunction "2_2") (pintype "passive"))
      (node (ref "C10") (pin "2") (pinfunction "2_2") (pintype "passive"))
      (node (ref "C11") (pin "2") (pinfunction "2_2") (pintype "passive"))
      (node (ref "C12") (pin "2") (pinfunction "2_2") (pintype "passive"))
      (node (ref "C13") (pin "2") (pinfunction "2_2") (pintype "passive"))
      (node (ref "C14") (pin "2") (pinfunction "2_2") (pintype "passive"))
      (node (ref "C15") (pin "2") (pinfunction "2_2") (pintype "passive"))
      (node (ref "C16") (pin "2") (pinfunction "2_2") (pintype "passive"))
      (node (ref "C17") (pin "2") (pinfunction "2_2") (pintype "passive"))
      (node (ref "C18") (pin "2") (pinfunction "2_2") (pintype "passive"))
      (node (ref "C19") (pin "2") (pinfunction "2_2") (pintype "passive"))
      (node (ref "C2") (pin "2") (pinfunction "2_2") (pintype "passive"))
      (node (ref "C4") (pin "2") (pinfunction "2_2") (pintype "passive"))
      (node (ref "C5") (pin "1") (pinfunction "1_1") (pintype "passive"))
      (node (ref "C6") (pin "2") (pinfunction "2_2") (pintype "passive"))
      (node (ref "C7") (pin "2") (pinfunction "2_2") (pintype "passive"))
      (node (ref "C8") (pin "2") (pinfunction "2_2") (pintype "passive"))
      (node (ref "C9") (pin "2") (pinfunction "2_2") (pintype "passive"))
      (node (ref "D4") (pin "1") (pinfunction "A_1") (pintype "passive"))
      (node (ref "DN1") (pin "2") (pinfunction "A_2") (pintype "passive"))
      (node (ref "DN2") (pin "2") (pinfunction "A_2") (pintype "passive"))
      (node (ref "J1") (pin "10") (pinfunction "GND_10") (pintype "power_in"))
      (node (ref "J1") (pin "4") (pinfunction "GND_4") (pintype "power_in"))
      (node (ref "J1") (pin "6") (pinfunction "GND_6") (pintype "power_in"))
      (node (ref "J1") (pin "8") (pinfunction "GND_8") (pintype "power_in"))
      (node (ref "J2") (pin "6") (pinfunction "6_6") (pintype "passive"))
      (node (ref "J3") (pin "2") (pinfunction "GND_2") (pintype "power_in"))
      (node (ref "J4") (pin "8") (pinfunction "8_8") (pintype "passive"))
      (node (ref "Q1") (pin "2") (pinfunction "S_2") (pintype "passive"))
      (node (ref "Q2") (pin "2") (pinfunction "S_2") (pintype "passive"))
      (node (ref "Q3") (pin "2") (pinfunction "S_2") (pintype "passive"))
      (node (ref "Q4") (pin "2") (pinfunction "S_2") (pintype "passive"))
      (node (ref "Q5") (pin "2") (pinfunction "S_2") (pintype "passive"))
      (node (ref "Q6") (pin "2") (pinfunction "S_2") (pintype "passive"))
      (node (ref "R13") (pin "1") (pinfunction "1_1") (pintype "passive"))
      (node (ref "R14") (pin "2") (pinfunction "2_2") (pintype "passive"))
      (node (ref "R19") (pin "1") (pinfunction "1_1") (pintype "passive"))
      (node (ref "R2") (pin "2") (pinfunction "2_2") (pintype "passive"))
      (node (ref "R3") (pin "2") (pinfunction "2_2") (pintype "passive"))
      (node (ref "R4") (pin "2") (pinfunction "2_2") (pintype "passive"))
      (node (ref "RN1") (pin "1") (pinfunction "1_1") (pintype "passive"))
      (node (ref "RN1") (pin "2") (pinfunction "1_2") (pintype "passive"))
      (node (ref "RN1") (pin "3") (pinfunction "1_3") (pintype "passive"))
      (node (ref "RN1") (pin "4") (pinfunction "1_4") (pintype "passive"))
      (node (ref "RN4") (pin "1") (pinfunction "1_1") (pintype "passive"))
      (node (ref "RN4") (pin "2") (pinfunction "1_2") (pintype "passive"))
      (node (ref "RN6") (pin "3") (pinfunction "1_3") (pintype "passive"))
      (node (ref "RN6") (pin "7") (pinfunction "2_7") (pintype "passive"))
      (node (ref "RN6") (pin "8") (pinfunction "2_8") (pintype "passive"))
      (node (ref "TP4") (pin "1") (pinfunction "P$1_1") (pintype "passive"))
      (node (ref "U1") (pin "21") (pinfunction "GND_21") (pintype "power_in"))
      (node (ref "U1") (pin "3") (pinfunction "GND_3") (pintype "power_in"))
      (node (ref "U1") (pin "5") (pinfunction "GND_5") (pintype "power_in"))
      (node (ref "U2") (pin "5") (pinfunction "GND_5") (pintype "power_in"))
      (node (ref "U3") (pin "4") (pinfunction "1_4") (pintype "input"))
      (node (ref "U3") (pin "5") (pinfunction "2_5") (pintype "input"))
      (node (ref "U3") (pin "9") (pinfunction "GND_9") (pintype "power_in"))
      (node (ref "U4") (pin "2") (pinfunction "GND_2") (pintype "power_in"))
      (node (ref "U4") (pin "8") (pinfunction "STBY_8") (pintype "passive"))
      (node (ref "U5") (pin "10") (pinfunction "GND_10") (pintype "power_in"))
      (node (ref "X1") (pin "2") (pinfunction "GND_2") (pintype "power_in"))
      (node (ref "X1") (pin "4") (pinfunction "GND_4") (pintype "power_in"))
      (node (ref "X2") (pin "2") (pinfunction "GND_2") (pintype "power_in"))
      (node (ref "X2") (pin "4") (pinfunction "GND_4") (pintype "power_in"))
    )
    (net (code "12") (name "INERTIA") (class "Default")
      (node (ref "D2") (pin "A") (pinfunction "A_A") (pintype "passive"))
      (node (ref "J4") (pin "6") (pinfunction "6_6") (pintype "passive"))
    )
    (net (code "13") (name "INERTIA_READ") (class "Default")
      (node (ref "R3") (pin "1") (pinfunction "1_1") (pintype "passive"))
      (node (ref "R6") (pin "2") (pinfunction "2_2") (pintype "passive"))
      (node (ref "U1") (pin "24") (pinfunction "15(A1)_24") (pintype "bidirectional"))
    )
    (net (code "14") (name "LED_AMS_CTRL") (class "Default")
      (node (ref "DN1") (pin "6") (pinfunction "C_6") (pintype "passive"))
      (node (ref "RN4") (pin "7") (pinfunction "2_7") (pintype "passive"))
      (node (ref "RN8") (pin "1") (pinfunction "1_1") (pintype "passive"))
      (node (ref "U1") (pin "30") (pinfunction "0_30") (pintype "bidirectional"))
    )
    (net (code "15") (name "LED_IMD_CTRL") (class "Default")
      (node (ref "DN1") (pin "4") (pinfunction "C_4") (pintype "passive"))
      (node (ref "RN1") (pin "8") (pinfunction "2_8") (pintype "passive"))
      (node (ref "RN2") (pin "4") (pinfunction "1_4") (pintype "passive"))
      (node (ref "U1") (pin "31") (pinfunction "1_31") (pintype "bidirectional"))
    )
    (net (code "16") (name "LED_MC_ERR_CTRL") (class "Default")
      (node (ref "DN1") (pin "3") (pinfunction "C_3") (pintype "passive"))
      (node (ref "RN1") (pin "6") (pinfunction "2_6") (pintype "passive"))
      (node (ref "RN2") (pin "1") (pinfunction "1_1") (pintype "passive"))
      (node (ref "U1") (pin "1") (pinfunction "3(PWM)_1") (pintype "bidirectional"))
    )
    (net (code "17") (name "LED_MODE_CTRL") (class "Default")
      (node (ref "DN1") (pin "5") (pinfunction "C_5") (pintype "passive"))
      (node (ref "RN1") (pin "7") (pinfunction "2_7") (pintype "passive"))
      (node (ref "RN2") (pin "3") (pinfunction "1_3") (pintype "passive"))
      (node (ref "U1") (pin "32") (pinfunction "2_32") (pintype "bidirectional"))
    )
    (net (code "18") (name "LED_START_CTRL") (class "Default")
      (node (ref "DN1") (pin "1") (pinfunction "C_1") (pintype "passive"))
      (node (ref "RN1") (pin "5") (pinfunction "2_5") (pintype "passive"))
      (node (ref "RN2") (pin "2") (pinfunction "1_2") (pintype "passive"))
      (node (ref "U1") (pin "2") (pinfunction "4_2") (pintype "bidirectional"))
    )
    (net (code "19") (name "Net-(A1-TRIM)") (class "Default")
      (node (ref "A1") (pin "6") (pinfunction "TRIM_6") (pintype "passive"))
      (node (ref "R19") (pin "2") (pinfunction "2_2") (pintype "passive"))
    )
    (net (code "20") (name "Net-(C13-Pad1)") (class "Default")
      (node (ref "C13") (pin "1") (pinfunction "1_1") (pintype "passive"))
      (node (ref "R18") (pin "1") (pinfunction "1_1") (pintype "passive"))
      (node (ref "R20") (pin "1") (pinfunction "1_1") (pintype "passive"))
    )
    (net (code "21") (name "Net-(D1-PadC)") (class "Default")
      (node (ref "D1") (pin "C") (pinfunction "C_C") (pintype "passive"))
      (node (ref "R5") (pin "1") (pinfunction "1_1") (pintype "passive"))
    )
    (net (code "22") (name "Net-(D2-PadC)") (class "Default")
      (node (ref "D2") (pin "C") (pinfunction "C_C") (pintype "passive"))
      (node (ref "R6") (pin "1") (pinfunction "1_1") (pintype "passive"))
    )
    (net (code "23") (name "Net-(D3-PadC)") (class "Default")
      (node (ref "D3") (pin "C") (pinfunction "C_C") (pintype "passive"))
      (node (ref "R7") (pin "1") (pinfunction "1_1") (pintype "passive"))
    )
    (net (code "24") (name "Net-(D5-A)") (class "Default")
      (node (ref "D5") (pin "2") (pinfunction "A_2") (pintype "passive"))
      (node (ref "U1") (pin "23") (pinfunction "14(A0)_23") (pintype "bidirectional"))
    )
    (net (code "25") (name "Net-(D5-C)") (class "Default")
      (node (ref "D5") (pin "1") (pinfunction "C_1") (pintype "passive"))
      (node (ref "RN6") (pin "6") (pinfunction "2_6") (pintype "passive"))
    )
    (net (code "26") (name "Net-(D6-C)") (class "Default")
      (node (ref "D6") (pin "1") (pinfunction "C_1") (pintype "passive"))
      (node (ref "RN6") (pin "1") (pinfunction "1_1") (pintype "passive"))
    )
    (net (code "27") (name "Net-(D7-C)") (class "Default")
      (node (ref "D7") (pin "1") (pinfunction "C_1") (pintype "passive"))
      (node (ref "RN6") (pin "2") (pinfunction "1_2") (pintype "passive"))
    )
    (net (code "28") (name "Net-(D100-PadC)") (class "Default")
      (node (ref "D100") (pin "C") (pinfunction "C_C") (pintype "passive"))
      (node (ref "R16") (pin "1") (pinfunction "1_1") (pintype "passive"))
    )
    (net (code "29") (name "Net-(D101-A)") (class "Default")
      (node (ref "D101") (pin "7") (pinfunction "A_7") (pintype "input"))
      (node (ref "RN7") (pin "8") (pinfunction "2_8") (pintype "passive"))
    )
    (net (code "30") (name "Net-(D101-B)") (class "Default")
      (node (ref "D101") (pin "6") (pinfunction "B_6") (pintype "input"))
      (node (ref "RN7") (pin "7") (pinfunction "2_7") (pintype "passive"))
    )
    (net (code "31") (name "Net-(D101-C)") (class "Default")
      (node (ref "D101") (pin "4") (pinfunction "C_4") (pintype "input"))
      (node (ref "RN7") (pin "6") (pinfunction "2_6") (pintype "passive"))
    )
    (net (code "32") (name "Net-(D101-D)") (class "Default")
      (node (ref "D101") (pin "2") (pinfunction "D_2") (pintype "input"))
      (node (ref "RN7") (pin "5") (pinfunction "2_5") (pintype "passive"))
    )
    (net (code "33") (name "Net-(D101-E)") (class "Default")
      (node (ref "D101") (pin "1") (pinfunction "E_1") (pintype "input"))
      (node (ref "RN5") (pin "8") (pinfunction "2_8") (pintype "passive"))
    )
    (net (code "34") (name "Net-(D101-F)") (class "Default")
      (node (ref "D101") (pin "9") (pinfunction "F_9") (pintype "input"))
      (node (ref "RN5") (pin "7") (pinfunction "2_7") (pintype "passive"))
    )
    (net (code "35") (name "Net-(D101-G)") (class "Default")
      (node (ref "D101") (pin "10") (pinfunction "G_10") (pintype "input"))
      (node (ref "RN5") (pin "6") (pinfunction "2_6") (pintype "passive"))
    )
    (net (code "36") (name "Net-(D102-PadC)") (class "Default")
      (node (ref "D102") (pin "C") (pinfunction "C_C") (pintype "passive"))
      (node (ref "R1") (pin "1") (pinfunction "1_1") (pintype "passive"))
    )
    (net (code "37") (name "Net-(D103-PadC)") (class "Default")
      (node (ref "D103") (pin "C") (pinfunction "C_C") (pintype "passive"))
      (node (ref "R17") (pin "1") (pinfunction "1_1") (pintype "passive"))
    )
    (net (code "38") (name "Net-(D104-PadC)") (class "Default")
      (node (ref "D104") (pin "C") (pinfunction "C_C") (pintype "passive"))
      (node (ref "R12") (pin "1") (pinfunction "1_1") (pintype "passive"))
    )
    (net (code "39") (name "Net-(D105-PadC)") (class "Default")
      (node (ref "D105") (pin "C") (pinfunction "C_C") (pintype "passive"))
      (node (ref "R8") (pin "1") (pinfunction "1_1") (pintype "passive"))
    )
    (net (code "40") (name "Net-(D106-PadC)") (class "Default")
      (node (ref "D106") (pin "C") (pinfunction "C_C") (pintype "passive"))
      (node (ref "R14") (pin "1") (pinfunction "1_1") (pintype "passive"))
    )
    (net (code "41") (name "Net-(D107-PadC)") (class "Default")
      (node (ref "D107") (pin "C") (pinfunction "C_C") (pintype "passive"))
      (node (ref "R22") (pin "1") (pinfunction "1_1") (pintype "passive"))
    )
    (net (code "42") (name "Net-(J1-CIPO)") (class "Default")
      (node (ref "J1") (pin "9") (pinfunction "CIPO_9") (pintype "bidirectional"))
      (node (ref "RN3") (pin "7") (pinfunction "2_7") (pintype "passive"))
      (node (ref "U3") (pin "3") (pinfunction "SDO_3") (pintype "output"))
      (node (ref "U5") (pin "17") (pinfunction "SDO_17") (pintype "output"))
    )
    (net (code "43") (name "Net-(J1-CLK)") (class "Default")
      (node (ref "J1") (pin "7") (pinfunction "CLK_7") (pintype "bidirectional"))
      (node (ref "RN3") (pin "8") (pinfunction "2_8") (pintype "passive"))
      (node (ref "U3") (pin "1") (pinfunction "CLK_1") (pintype "input"))
      (node (ref "U5") (pin "14") (pinfunction "CLK_14") (pintype "input"))
    )
    (net (code "44") (name "Net-(J1-COPI)") (class "Default")
      (node (ref "J1") (pin "1") (pinfunction "COPI_1") (pintype "bidirectional"))
      (node (ref "RN3") (pin "6") (pinfunction "2_6") (pintype "passive"))
      (node (ref "U3") (pin "2") (pinfunction "SDI_2") (pintype "input"))
      (node (ref "U5") (pin "16") (pinfunction "SDI_16") (pintype "input"))
    )
    (net (code "45") (name "Net-(J4-Pad1)") (class "Default")
      (node (ref "J4") (pin "1") (pinfunction "1_1") (pintype "passive"))
      (node (ref "XF1") (pin "1") (pinfunction "1_1") (pintype "passive"))
      (node (ref "XF1") (pin "2") (pinfunction "1_2") (pintype "passive"))
    )
    (net (code "46") (name "Net-(J5-P$1)") (class "Default")
      (node (ref "J5") (pin "1") (pinfunction "P$1_1") (pintype "passive"))
      (node (ref "R20") (pin "2") (pinfunction "2_2") (pintype "passive"))
    )
    (net (code "47") (name "Net-(J5-P$2)") (class "Default")
      (node (ref "J5") (pin "2") (pinfunction "P$2_2") (pintype "passive"))
      (node (ref "U4") (pin "4") (pinfunction "RXD_4") (pintype "output"))
      (node (ref "U5") (pin "2") (pinfunction "RX_2") (pintype "input"))
    )
    (net (code "48") (name "Net-(LS100-FEEDBACK)") (class "Default")
      (node (ref "LS100") (pin "F") (pinfunction "FEEDBACK_F") (pintype "bidirectional"))
      (node (ref "R15") (pin "2") (pinfunction "2_2") (pintype "passive"))
    )
    (net (code "49") (name "Net-(LS100-GND)") (class "Default")
      (node (ref "LS100") (pin "G") (pinfunction "GND_G") (pintype "power_in"))
      (node (ref "R10") (pin "1") (pinfunction "1_1") (pintype "passive"))
      (node (ref "U2") (pin "6") (pinfunction "HORNB_6") (pintype "output"))
    )
    (net (code "50") (name "Net-(LS100-MAIN)") (class "Default")
      (node (ref "C3") (pin "1") (pinfunction "1_1") (pintype "passive"))
      (node (ref "LS100") (pin "M") (pinfunction "MAIN_M") (pintype "power_in"))
      (node (ref "U2") (pin "7") (pinfunction "HORNS_7") (pintype "output"))
    )
    (net (code "51") (name "Net-(Q1-D)") (class "Default")
      (node (ref "Q1") (pin "3") (pinfunction "D_3") (pintype "passive"))
      (node (ref "R1") (pin "2") (pinfunction "2_2") (pintype "passive"))
    )
    (net (code "52") (name "Net-(Q1-G)") (class "Default")
      (node (ref "Q1") (pin "1") (pinfunction "G_1") (pintype "passive"))
      (node (ref "RN2") (pin "8") (pinfunction "2_8") (pintype "passive"))
    )
    (net (code "53") (name "Net-(Q2-D)") (class "Default")
      (node (ref "Q2") (pin "3") (pinfunction "D_3") (pintype "passive"))
      (node (ref "R8") (pin "2") (pinfunction "2_2") (pintype "passive"))
    )
    (net (code "54") (name "Net-(Q2-G)") (class "Default")
      (node (ref "Q2") (pin "1") (pinfunction "G_1") (pintype "passive"))
      (node (ref "RN2") (pin "7") (pinfunction "2_7") (pintype "passive"))
    )
    (net (code "55") (name "Net-(Q3-D)") (class "Default")
      (node (ref "Q3") (pin "3") (pinfunction "D_3") (pintype "passive"))
      (node (ref "R12") (pin "2") (pinfunction "2_2") (pintype "passive"))
    )
    (net (code "56") (name "Net-(Q3-G)") (class "Default")
      (node (ref "Q3") (pin "1") (pinfunction "G_1") (pintype "passive"))
      (node (ref "RN2") (pin "6") (pinfunction "2_6") (pintype "passive"))
    )
    (net (code "57") (name "Net-(Q4-D)") (class "Default")
      (node (ref "Q4") (pin "3") (pinfunction "D_3") (pintype "passive"))
      (node (ref "R16") (pin "2") (pinfunction "2_2") (pintype "passive"))
    )
    (net (code "58") (name "Net-(Q4-G)") (class "Default")
      (node (ref "Q4") (pin "1") (pinfunction "G_1") (pintype "passive"))
      (node (ref "RN2") (pin "5") (pinfunction "2_5") (pintype "passive"))
    )
    (net (code "59") (name "Net-(Q5-D)") (class "Default")
      (node (ref "Q5") (pin "3") (pinfunction "D_3") (pintype "passive"))
      (node (ref "R17") (pin "2") (pinfunction "2_2") (pintype "passive"))
    )
    (net (code "60") (name "Net-(Q5-G)") (class "Default")
      (node (ref "Q5") (pin "1") (pinfunction "G_1") (pintype "passive"))
      (node (ref "RN8") (pin "7") (pinfunction "2_7") (pintype "passive"))
    )
    (net (code "61") (name "Net-(Q6-D)") (class "Default")
      (node (ref "Q6") (pin "3") (pinfunction "D_3") (pintype "passive"))
      (node (ref "R22") (pin "2") (pinfunction "2_2") (pintype "passive"))
    )
    (net (code "62") (name "Net-(Q6-G)") (class "Default")
      (node (ref "Q6") (pin "1") (pinfunction "G_1") (pintype "passive"))
      (node (ref "RN8") (pin "8") (pinfunction "2_8") (pintype "passive"))
    )
    (net (code "63") (name "Net-(RN3B-1)") (class "Default")
      (node (ref "RN3") (pin "2") (pinfunction "1_2") (pintype "passive"))
      (node (ref "U1") (pin "16") (pinfunction "(CIPO)12_16") (pintype "bidirectional"))
    )
    (net (code "64") (name "Net-(RN3C-1)") (class "Default")
      (node (ref "RN3") (pin "3") (pinfunction "1_3") (pintype "passive"))
      (node (ref "U1") (pin "15") (pinfunction "(PWM/COPI)11_15") (pintype "bidirectional"))
    )
    (net (code "65") (name "Net-(RN3D-1)") (class "Default")
      (node (ref "RN3") (pin "4") (pinfunction "1_4") (pintype "passive"))
      (node (ref "U1") (pin "14") (pinfunction "(PWM/CS)10_14") (pintype "bidirectional"))
    )
    (net (code "66") (name "Net-(RN3D-2)") (class "Default")
      (node (ref "RN3") (pin "5") (pinfunction "2_5") (pintype "passive"))
      (node (ref "U5") (pin "18") (pinfunction "~{CS}_18") (pintype "input"))
    )
    (net (code "67") (name "Net-(RN5B-1)") (class "Default")
      (node (ref "RN5") (pin "2") (pinfunction "1_2") (pintype "passive"))
      (node (ref "U3") (pin "17") (pinfunction "GPA5_17") (pintype "bidirectional"))
    )
    (net (code "68") (name "Net-(RN5C-1)") (class "Default")
      (node (ref "RN5") (pin "3") (pinfunction "1_3") (pintype "passive"))
      (node (ref "U3") (pin "18") (pinfunction "GPA6_18") (pintype "bidirectional"))
    )
    (net (code "69") (name "Net-(RN7B-1)") (class "Default")
      (node (ref "RN7") (pin "2") (pinfunction "1_2") (pintype "passive"))
      (node (ref "U3") (pin "13") (pinfunction "GPA1_13") (pintype "bidirectional"))
    )
    (net (code "70") (name "Net-(RN7C-1)") (class "Default")
      (node (ref "RN7") (pin "3") (pinfunction "1_3") (pintype "passive"))
      (node (ref "U3") (pin "14") (pinfunction "GPA2_14") (pintype "bidirectional"))
    )
    (net (code "71") (name "Net-(RN7D-1)") (class "Default")
      (node (ref "RN7") (pin "4") (pinfunction "1_4") (pintype "passive"))
      (node (ref "U3") (pin "15") (pinfunction "GPA3_15") (pintype "bidirectional"))
    )
    (net (code "72") (name "Net-(U1-(CLK)13)") (class "Default")
      (node (ref "RN3") (pin "1") (pinfunction "1_1") (pintype "passive"))
      (node (ref "U1") (pin "17") (pinfunction "(CLK)13_17") (pintype "bidirectional"))
    )
    (net (code "73") (name "Net-(U1-(XTAL1)14)") (class "Default")
      (node (ref "C2") (pin "1") (pinfunction "1_1") (pintype "passive"))
      (node (ref "U1") (pin "7") (pinfunction "(XTAL1)14_7") (pintype "bidirectional"))
      (node (ref "X1") (pin "1") (pinfunction "1_1") (pintype "passive"))
    )
    (net (code "74") (name "Net-(U1-(XTAL2)15)") (class "Default")
      (node (ref "C1") (pin "1") (pinfunction "1_1") (pintype "passive"))
      (node (ref "U1") (pin "8") (pinfunction "(XTAL2)15_8") (pintype "bidirectional"))
      (node (ref "X1") (pin "3") (pinfunction "3_3") (pintype "passive"))
    )
    (net (code "75") (name "Net-(U1-8)") (class "Default")
      (node (ref "R9") (pin "1") (pinfunction "1_1") (pintype "passive"))
      (node (ref "U1") (pin "12") (pinfunction "8_12") (pintype "bidirectional"))
    )
    (net (code "76") (name "Net-(U1-AREF)") (class "Default")
      (node (ref "C7") (pin "1") (pinfunction "1_1") (pintype "passive"))
      (node (ref "U1") (pin "20") (pinfunction "AREF_20") (pintype "input"))
    )
    (net (code "77") (name "Net-(U1-AVDD)") (class "Default")
      (node (ref "C6") (pin "1") (pinfunction "1_1") (pintype "passive"))
      (node (ref "L1") (pin "1") (pinfunction "1_1") (pintype "passive"))
      (node (ref "U1") (pin "18") (pinfunction "AVDD_18") (pintype "power_in"))
    )
    (net (code "78") (name "Net-(U2-FEED)") (class "Default")
      (node (ref "C3") (pin "2") (pinfunction "2_2") (pintype "passive"))
      (node (ref "R10") (pin "2") (pinfunction "2_2") (pintype "passive"))
      (node (ref "R15") (pin "1") (pinfunction "1_1") (pintype "passive"))
      (node (ref "U2") (pin "4") (pinfunction "FEED_4") (pintype "input"))
    )
    (net (code "79") (name "Net-(U3-GPA0)") (class "Default")
      (node (ref "RN7") (pin "1") (pinfunction "1_1") (pintype "passive"))
      (node (ref "U3") (pin "12") (pinfunction "GPA0_12") (pintype "bidirectional"))
    )
    (net (code "80") (name "Net-(U3-GPA4)") (class "Default")
      (node (ref "RN5") (pin "1") (pinfunction "1_1") (pintype "passive"))
      (node (ref "U3") (pin "16") (pinfunction "GPA4_16") (pintype "bidirectional"))
    )
    (net (code "81") (name "Net-(U3-~{CS})") (class "Default")
      (node (ref "R9") (pin "2") (pinfunction "2_2") (pintype "passive"))
      (node (ref "U3") (pin "7") (pinfunction "~{CS}_7") (pintype "input"))
    )
    (net (code "82") (name "Net-(U4-TXD)") (class "Default")
      (node (ref "R18") (pin "2") (pinfunction "2_2") (pintype "passive"))
      (node (ref "U4") (pin "1") (pinfunction "TXD_1") (pintype "input"))
      (node (ref "U5") (pin "1") (pinfunction "TX_1") (pintype "output"))
    )
    (net (code "83") (name "Net-(U5-OSC1)") (class "Default")
      (node (ref "C18") (pin "1") (pinfunction "1_1") (pintype "passive"))
      (node (ref "U5") (pin "9") (pinfunction "OSC1_9") (pintype "bidirectional"))
      (node (ref "X2") (pin "1") (pinfunction "1_1") (pintype "passive"))
    )
    (net (code "84") (name "Net-(U5-OSC2)") (class "Default")
      (node (ref "C19") (pin "1") (pinfunction "1_1") (pintype "passive"))
      (node (ref "U5") (pin "8") (pinfunction "OSC2_8") (pintype "bidirectional"))
      (node (ref "X2") (pin "3") (pinfunction "3_3") (pintype "passive"))
    )
    (net (code "85") (name "Net-(U5-~{RESET})") (class "Default")
      (node (ref "R21") (pin "2") (pinfunction "2_2") (pintype "passive"))
      (node (ref "U5") (pin "19") (pinfunction "~{RESET}_19") (pintype "input"))
    )
    (net (code "86") (name "RESET") (class "Default")
      (node (ref "J1") (pin "5") (pinfunction "RESET_5") (pintype "output"))
      (node (ref "R11") (pin "2") (pinfunction "2_2") (pintype "passive"))
      (node (ref "U1") (pin "29") (pinfunction "22(~{RESET})_29") (pintype "bidirectional"))
    )
    (net (code "87") (name "SHUTDOWN_H") (class "Default")
      (node (ref "D3") (pin "A") (pinfunction "A_A") (pintype "passive"))
      (node (ref "J4") (pin "5") (pinfunction "5_5") (pintype "passive"))
    )
    (net (code "88") (name "SHUTDOWN_H_READ") (class "Default")
      (node (ref "R4") (pin "1") (pinfunction "1_1") (pintype "passive"))
      (node (ref "R7") (pin "2") (pinfunction "2_2") (pintype "passive"))
      (node (ref "U1") (pin "22") (pinfunction "A7_22") (pintype "bidirectional"))
    )
    (net (code "89") (name "SOC") (class "Default")
      (node (ref "DN2") (pin "1") (pinfunction "C_1") (pintype "passive"))
      (node (ref "RN4") (pin "8") (pinfunction "2_8") (pintype "passive"))
      (node (ref "RN8") (pin "2") (pinfunction "1_2") (pintype "passive"))
      (node (ref "U1") (pin "28") (pinfunction "19(A5)_28") (pintype "bidirectional"))
    )
    (net (code "90") (name "SSOK") (class "Default")
      (node (ref "D1") (pin "A") (pinfunction "A_A") (pintype "passive"))
      (node (ref "D106") (pin "A") (pinfunction "A_A") (pintype "passive"))
      (node (ref "J4") (pin "7") (pinfunction "7_7") (pintype "passive"))
      (node (ref "TP1") (pin "1") (pinfunction "P$1_1") (pintype "passive"))
    )
    (net (code "91") (name "SSOK_READ") (class "Default")
      (node (ref "R2") (pin "1") (pinfunction "1_1") (pintype "passive"))
      (node (ref "R5") (pin "2") (pinfunction "2_2") (pintype "passive"))
      (node (ref "U1") (pin "19") (pinfunction "A6_19") (pintype "bidirectional"))
    )
    (net (code "92") (name "unconnected-(A1-EN-Pad1)") (class "Default")
      (node (ref "A1") (pin "1") (pinfunction "EN_1") (pintype "input"))
    )
    (net (code "93") (name "unconnected-(J4-Pad2)") (class "Default")
      (node (ref "J4") (pin "2") (pinfunction "2_2") (pintype "passive"))
    )
    (net (code "94") (name "unconnected-(U1-5(PWM)-Pad9)") (class "Default")
      (node (ref "U1") (pin "9") (pinfunction "5(PWM)_9") (pintype "bidirectional"))
    )
    (net (code "95") (name "unconnected-(U3-GPA7-Pad19)") (class "Default")
      (node (ref "U3") (pin "19") (pinfunction "GPA7_19") (pintype "bidirectional"))
    )
    (net (code "96") (name "unconnected-(U3-INT-Pad8)") (class "Default")
      (node (ref "U3") (pin "8") (pinfunction "INT_8") (pintype "output"))
    )
    (net (code "97") (name "unconnected-(U5-CLKOUT-Pad3)") (class "Default")
      (node (ref "U5") (pin "3") (pinfunction "CLKOUT_3") (pintype "output"))
    )
    (net (code "98") (name "unconnected-(U5-~{INT}-Pad13)") (class "Default")
      (node (ref "U5") (pin "13") (pinfunction "~{INT}_13") (pintype "output"))
    )
    (net (code "99") (name "unconnected-(U5-~{RX0BF}-Pad12)") (class "Default")
      (node (ref "U5") (pin "12") (pinfunction "~{RX0BF}_12") (pintype "output"))
    )
    (net (code "100") (name "unconnected-(U5-~{RX1BF}-Pad11)") (class "Default")
      (node (ref "U5") (pin "11") (pinfunction "~{RX1BF}_11") (pintype "output"))
    )
    (net (code "101") (name "unconnected-(U5-~{TX0RTS}-Pad4)") (class "Default")
      (node (ref "U5") (pin "4") (pinfunction "~{TX0RTS}_4") (pintype "input"))
    )
    (net (code "102") (name "unconnected-(U5-~{TX1RTS}-Pad5)") (class "Default")
      (node (ref "U5") (pin "5") (pinfunction "~{TX1RTS}_5") (pintype "input"))
    )
    (net (code "103") (name "unconnected-(U5-~{TX2RTS}-Pad7)") (class "Default")
      (node (ref "U5") (pin "7") (pinfunction "~{TX2RTS}_7") (pintype "input"))
    )
  )
)
